# esp8266_ver3.net
KiCad netlist of a schematic drawn in EAGLE
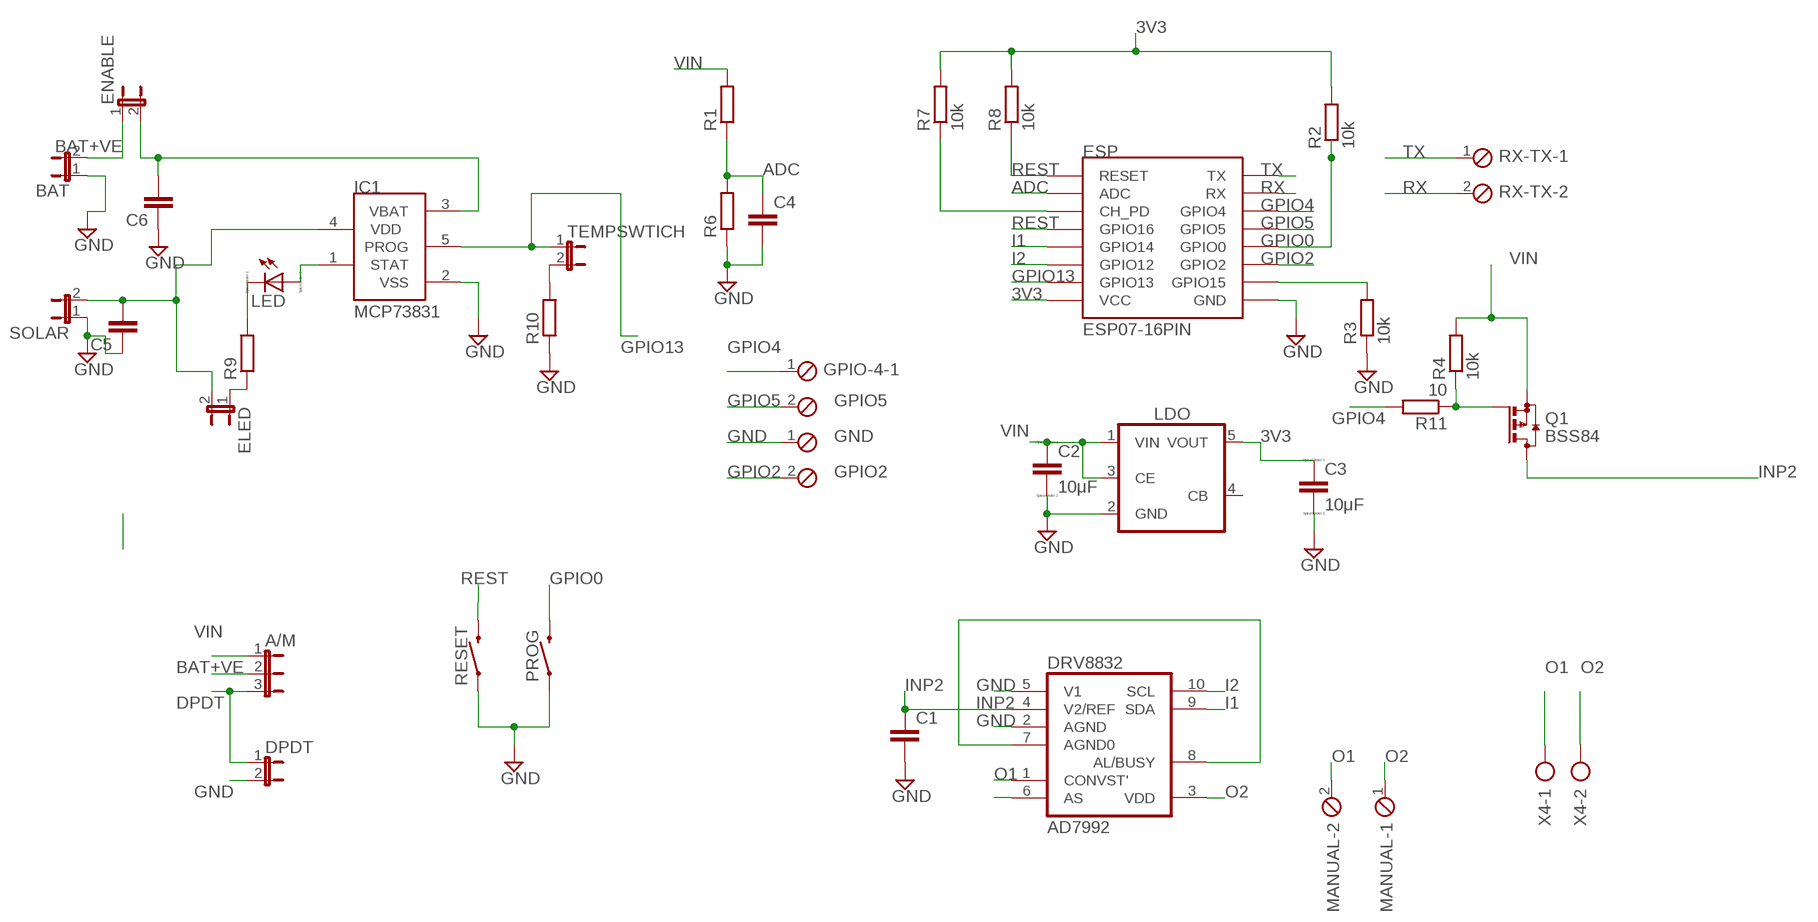
[diagram p0: schematic, sheet 1]

(export (version "E")
  (design (tool "Eeschema 10.0.6"))
  (components
    (comp (ref "A/M")
      (value "JP2E")
      (footprint "eagle-import:JP2")
      (libsource (lib "eagle-import") (part "JP2E"))
    )
    (comp (ref "BAT")
      (value "JP1E")
      (footprint "eagle-import:JP1")
      (libsource (lib "eagle-import") (part "JP1E"))
    )
    (comp (ref "C1")
      (value "C-EUC0805K")
      (footprint "eagle-import:C0805K")
      (libsource (lib "eagle-import") (part "C-EUC0805K"))
    )
    (comp (ref "C2")
      (value "10μF")
      (footprint "eagle-import:C1206")
      (libsource (lib "eagle-import") (part "CC1206"))
    )
    (comp (ref "C3")
      (value "10μF")
      (footprint "eagle-import:C1206")
      (libsource (lib "eagle-import") (part "CC1206"))
    )
    (comp (ref "C4")
      (value "C-EUC1206")
      (footprint "eagle-import:C1206")
      (libsource (lib "eagle-import") (part "C-EUC1206"))
    )
    (comp (ref "C5")
      (value "C-EUC1206")
      (footprint "eagle-import:C1206")
      (libsource (lib "eagle-import") (part "C-EUC1206"))
    )
    (comp (ref "C6")
      (value "C-EUC1206")
      (footprint "eagle-import:C1206")
      (libsource (lib "eagle-import") (part "C-EUC1206"))
    )
    (comp (ref "DPDT")
      (value "JP1E")
      (footprint "eagle-import:JP1")
      (libsource (lib "eagle-import") (part "JP1E"))
    )
    (comp (ref "DRV8832")
      (value "AD7992")
      (footprint "eagle-import:MSOP10")
      (libsource (lib "eagle-import") (part "AD7992"))
    )
    (comp (ref "ELED")
      (value "JP1E")
      (footprint "eagle-import:JP1")
      (libsource (lib "eagle-import") (part "JP1E"))
    )
    (comp (ref "ENABLE")
      (value "JP1E")
      (footprint "eagle-import:JP1")
      (libsource (lib "eagle-import") (part "JP1E"))
    )
    (comp (ref "ESP")
      (value "ESP07-16PIN")
      (footprint "eagle-import:ESP07-16PIN")
      (libsource (lib "eagle-import") (part "ESP07-16PIN"))
    )
    (comp (ref "GPIO-4")
      (value "MPT2")
      (footprint "eagle-import:2POL254")
      (libsource (lib "eagle-import") (part "con-phoenix-254_172_MPT2"))
    )
    (comp (ref "IC1")
      (value "MCP73831")
      (footprint "eagle-import:SOT23-5L")
      (libsource (lib "eagle-import") (part "MCP73831"))
    )
    (comp (ref "LDO")
      (value "TS5205")
      (footprint "eagle-import:SOT25")
      (libsource (lib "eagle-import") (part "TS5205"))
    )
    (comp (ref "LED")
      (value "LED_E")
      (footprint "eagle-import:LED_1206")
      (libsource (lib "eagle-import") (part "LED_E"))
    )
    (comp (ref "MANUAL")
      (value "MPT2")
      (footprint "eagle-import:2POL254")
      (libsource (lib "eagle-import") (part "con-phoenix-254_172_MPT2"))
    )
    (comp (ref "PROG")
      (value "MOMENTARY-SWITCH-SPST-SMD-5.2MM")
      (footprint "eagle-import:TACTILE_SWITCH_SMD_5.2MM")
      (libsource (lib "eagle-import") (part "MOMENTARY-SWITCH-SPST-SMD-5.2MM"))
    )
    (comp (ref "Q1")
      (value "BSS84")
      (footprint "eagle-import:SOT23")
      (libsource (lib "eagle-import") (part "BSS84"))
    )
    (comp (ref "R1")
      (value "R-EU_R1206")
      (footprint "eagle-import:R1206")
      (libsource (lib "eagle-import") (part "resistor_348_R-EU_R1206"))
    )
    (comp (ref "R2")
      (value "10k")
      (footprint "eagle-import:R1206")
      (libsource (lib "eagle-import") (part "R-EU_R1206"))
    )
    (comp (ref "R3")
      (value "10k")
      (footprint "eagle-import:R1206")
      (libsource (lib "eagle-import") (part "R-EU_R1206"))
    )
    (comp (ref "R4")
      (value "10k")
      (footprint "eagle-import:R1206")
      (libsource (lib "eagle-import") (part "resistor_348_R-EU_R1206"))
    )
    (comp (ref "R6")
      (value "R-EU_R1206")
      (footprint "eagle-import:R1206")
      (libsource (lib "eagle-import") (part "resistor_348_R-EU_R1206"))
    )
    (comp (ref "R7")
      (value "10k")
      (footprint "eagle-import:R1206")
      (libsource (lib "eagle-import") (part "R-EU_R1206"))
    )
    (comp (ref "R8")
      (value "10k")
      (footprint "eagle-import:R1206")
      (libsource (lib "eagle-import") (part "R-EU_R1206"))
    )
    (comp (ref "R9")
      (value "R-EU_R1206")
      (footprint "eagle-import:R1206")
      (libsource (lib "eagle-import") (part "resistor_348_R-EU_R1206"))
    )
    (comp (ref "R10")
      (value "R-EU_R1206")
      (footprint "eagle-import:R1206")
      (libsource (lib "eagle-import") (part "resistor_348_R-EU_R1206"))
    )
    (comp (ref "R11")
      (value "10")
      (footprint "eagle-import:R1206")
      (libsource (lib "eagle-import") (part "resistor_348_R-EU_R1206"))
    )
    (comp (ref "RESET")
      (value "MOMENTARY-SWITCH-SPST-SMD-5.2MM")
      (footprint "eagle-import:TACTILE_SWITCH_SMD_5.2MM")
      (libsource (lib "eagle-import") (part "MOMENTARY-SWITCH-SPST-SMD-5.2MM"))
    )
    (comp (ref "RX-TX")
      (value "MPT2")
      (footprint "eagle-import:2POL254")
      (libsource (lib "eagle-import") (part "MPT2"))
    )
    (comp (ref "SOLAR")
      (value "JP1E")
      (footprint "eagle-import:JP1")
      (libsource (lib "eagle-import") (part "JP1E"))
    )
    (comp (ref "TEMPSWTICH")
      (value "JP1E")
      (footprint "eagle-import:JP1")
      (libsource (lib "eagle-import") (part "JP1E"))
    )
    (comp (ref "X2")
      (value "MPT2")
      (footprint "eagle-import:2POL254")
      (libsource (lib "eagle-import") (part "con-phoenix-254_172_MPT2"))
    )
    (comp (ref "X4")
      (value "AK300/2")
      (footprint "eagle-import:AK300_2")
      (libsource (lib "eagle-import") (part "AK300/2"))
    )
  )
  (nets
    (net (code "1") (name "/3V3") (class "Default")
      (node (ref "C3") (pin "1") (pinfunction "1_1") (pintype "passive"))
      (node (ref "ESP") (pin "VCC") (pinfunction "VCC_VCC") (pintype "bidirectional"))
      (node (ref "LDO") (pin "5") (pinfunction "VOUT_5") (pintype "passive"))
      (node (ref "R2") (pin "2") (pinfunction "2_2") (pintype "passive"))
      (node (ref "R7") (pin "2") (pinfunction "2_2") (pintype "passive"))
      (node (ref "R8") (pin "2") (pinfunction "2_2") (pintype "passive"))
    )
    (net (code "2") (name "/ADC") (class "Default")
      (node (ref "C4") (pin "1") (pinfunction "1_1") (pintype "passive"))
      (node (ref "ESP") (pin "ADC") (pinfunction "ADC_ADC") (pintype "bidirectional"))
      (node (ref "R1") (pin "1") (pinfunction "1_1") (pintype "passive"))
      (node (ref "R6") (pin "2") (pinfunction "2_2") (pintype "passive"))
    )
    (net (code "3") (name "/BAT+VE") (class "Default")
      (node (ref "A/M") (pin "2") (pinfunction "2_2") (pintype "passive"))
      (node (ref "BAT") (pin "2") (pinfunction "2_2") (pintype "passive"))
      (node (ref "ENABLE") (pin "1") (pinfunction "1_1") (pintype "passive"))
    )
    (net (code "4") (name "/DPDT") (class "Default")
      (node (ref "A/M") (pin "3") (pinfunction "3_3") (pintype "passive"))
      (node (ref "DPDT") (pin "1") (pinfunction "1_1") (pintype "passive"))
    )
    (net (code "5") (name "/GPIO0") (class "Default")
      (node (ref "ESP") (pin "GPIO0") (pinfunction "GPIO0_GPIO0") (pintype "bidirectional"))
      (node (ref "PROG") (pin "3") (pinfunction "2_3") (pintype "passive"))
      (node (ref "R2") (pin "1") (pinfunction "1_1") (pintype "passive"))
    )
    (net (code "6") (name "/GPIO2") (class "Default")
      (node (ref "ESP") (pin "GPIO2") (pinfunction "GPIO2_GPIO2") (pintype "bidirectional"))
      (node (ref "X2") (pin "2") (pinfunction "1_2") (pintype "passive"))
    )
    (net (code "7") (name "/GPIO4") (class "Default")
      (node (ref "ESP") (pin "GPIO4") (pinfunction "GPIO4_GPIO4") (pintype "bidirectional"))
      (node (ref "GPIO-4") (pin "1") (pinfunction "1_1") (pintype "passive"))
      (node (ref "R11") (pin "2") (pinfunction "2_2") (pintype "passive"))
    )
    (net (code "8") (name "/GPIO5") (class "Default")
      (node (ref "ESP") (pin "GPIO5") (pinfunction "GPIO5_GPIO5") (pintype "bidirectional"))
      (node (ref "GPIO-4") (pin "2") (pinfunction "1_2") (pintype "passive"))
    )
    (net (code "9") (name "/GPIO13") (class "Default")
      (node (ref "ESP") (pin "GPIO13") (pinfunction "GPIO13_GPIO13") (pintype "bidirectional"))
      (node (ref "IC1") (pin "5") (pinfunction "PROG_5") (pintype "bidirectional"))
      (node (ref "TEMPSWTICH") (pin "1") (pinfunction "1_1") (pintype "passive"))
    )
    (net (code "10") (name "/I1") (class "Default")
      (node (ref "DRV8832") (pin "9") (pinfunction "SDA_9") (pintype "output"))
      (node (ref "ESP") (pin "GPIO14") (pinfunction "GPIO14_GPIO14") (pintype "bidirectional"))
    )
    (net (code "11") (name "/I2") (class "Default")
      (node (ref "DRV8832") (pin "10") (pinfunction "SCL_10") (pintype "output"))
      (node (ref "ESP") (pin "GPIO12") (pinfunction "GPIO12_GPIO12") (pintype "bidirectional"))
    )
    (net (code "12") (name "/INP2") (class "Default")
      (node (ref "C1") (pin "1") (pinfunction "1_1") (pintype "passive"))
      (node (ref "DRV8832") (pin "4") (pinfunction "V2/REF_4") (pintype "input"))
      (node (ref "Q1") (pin "3") (pinfunction "D_3") (pintype "passive"))
    )
    (net (code "13") (name "/O1") (class "Default")
      (node (ref "DRV8832") (pin "1") (pinfunction "CONVST'_1") (pintype "input"))
      (node (ref "MANUAL") (pin "2") (pinfunction "1_2") (pintype "passive"))
      (node (ref "X4") (pin "1") (pinfunction "KL_1") (pintype "passive"))
    )
    (net (code "14") (name "/O2") (class "Default")
      (node (ref "DRV8832") (pin "3") (pinfunction "VDD_3") (pintype "power_in"))
      (node (ref "MANUAL") (pin "1") (pinfunction "1_1") (pintype "passive"))
      (node (ref "X4") (pin "2") (pinfunction "KL_2") (pintype "passive"))
    )
    (net (code "15") (name "/REST") (class "Default")
      (node (ref "ESP") (pin "GPIO16") (pinfunction "GPIO16_GPIO16") (pintype "bidirectional"))
      (node (ref "ESP") (pin "REST") (pinfunction "RESET_REST") (pintype "bidirectional"))
      (node (ref "R8") (pin "1") (pinfunction "1_1") (pintype "passive"))
      (node (ref "RESET") (pin "3") (pinfunction "2_3") (pintype "passive"))
    )
    (net (code "16") (name "/RX") (class "Default")
      (node (ref "ESP") (pin "RX") (pinfunction "RX_RX") (pintype "bidirectional"))
      (node (ref "RX-TX") (pin "2") (pinfunction "1_2") (pintype "passive"))
    )
    (net (code "17") (name "/TX") (class "Default")
      (node (ref "ESP") (pin "TX") (pinfunction "TX_TX") (pintype "bidirectional"))
      (node (ref "RX-TX") (pin "1") (pinfunction "1_1") (pintype "passive"))
    )
    (net (code "18") (name "/VIN") (class "Default")
      (node (ref "A/M") (pin "1") (pinfunction "1_1") (pintype "passive"))
      (node (ref "C2") (pin "1") (pinfunction "1_1") (pintype "passive"))
      (node (ref "LDO") (pin "1") (pinfunction "VIN_1") (pintype "input"))
      (node (ref "LDO") (pin "3") (pinfunction "CE_3") (pintype "input"))
      (node (ref "Q1") (pin "2") (pinfunction "S_2") (pintype "passive"))
      (node (ref "R1") (pin "2") (pinfunction "2_2") (pintype "passive"))
      (node (ref "R4") (pin "2") (pinfunction "2_2") (pintype "passive"))
    )
    (net (code "19") (name "GND") (class "Default")
      (node (ref "BAT") (pin "1") (pinfunction "1_1") (pintype "passive"))
      (node (ref "C1") (pin "2") (pinfunction "2_2") (pintype "passive"))
      (node (ref "C2") (pin "2") (pinfunction "2_2") (pintype "passive"))
      (node (ref "C3") (pin "2") (pinfunction "2_2") (pintype "passive"))
      (node (ref "C4") (pin "2") (pinfunction "2_2") (pintype "passive"))
      (node (ref "C5") (pin "1") (pinfunction "1_1") (pintype "passive"))
      (node (ref "C6") (pin "1") (pinfunction "1_1") (pintype "passive"))
      (node (ref "DPDT") (pin "2") (pinfunction "2_2") (pintype "passive"))
      (node (ref "DRV8832") (pin "2") (pinfunction "AGND_2") (pintype "power_in"))
      (node (ref "DRV8832") (pin "5") (pinfunction "V1_5") (pintype "input"))
      (node (ref "ESP") (pin "GND") (pinfunction "GND_GND") (pintype "bidirectional"))
      (node (ref "IC1") (pin "2") (pinfunction "VSS_2") (pintype "bidirectional"))
      (node (ref "LDO") (pin "2") (pinfunction "GND_2") (pintype "passive"))
      (node (ref "PROG") (pin "1") (pinfunction "1_1") (pintype "passive"))
      (node (ref "R10") (pin "1") (pinfunction "1_1") (pintype "passive"))
      (node (ref "R3") (pin "1") (pinfunction "1_1") (pintype "passive"))
      (node (ref "R6") (pin "1") (pinfunction "1_1") (pintype "passive"))
      (node (ref "RESET") (pin "1") (pinfunction "1_1") (pintype "passive"))
      (node (ref "SOLAR") (pin "1") (pinfunction "1_1") (pintype "passive"))
      (node (ref "X2") (pin "1") (pinfunction "1_1") (pintype "passive"))
    )
    (net (code "20") (name "Net-(DRV8832-AGND0)") (class "Default")
      (node (ref "DRV8832") (pin "7") (pinfunction "AGND0_7") (pintype "power_in"))
      (node (ref "DRV8832") (pin "8") (pinfunction "AL/BUSY_8") (pintype "output"))
    )
    (net (code "21") (name "Net-(ELED-Pad1)") (class "Default")
      (node (ref "ELED") (pin "1") (pinfunction "1_1") (pintype "passive"))
      (node (ref "R9") (pin "1") (pinfunction "1_1") (pintype "passive"))
    )
    (net (code "22") (name "Net-(ESP-PadCH_PD)") (class "Default")
      (node (ref "ESP") (pin "CH_PD") (pinfunction "CH_PD_CH_PD") (pintype "bidirectional"))
      (node (ref "R7") (pin "1") (pinfunction "1_1") (pintype "passive"))
    )
    (net (code "23") (name "Net-(ESP-PadGPIO15)") (class "Default")
      (node (ref "ESP") (pin "GPIO15") (pinfunction "GPIO15_GPIO15") (pintype "bidirectional"))
      (node (ref "R3") (pin "2") (pinfunction "2_2") (pintype "passive"))
    )
    (net (code "24") (name "Net-(IC1-STAT)") (class "Default")
      (node (ref "IC1") (pin "1") (pinfunction "STAT_1") (pintype "bidirectional"))
      (node (ref "LED") (pin "A") (pinfunction "A_A") (pintype "passive"))
    )
    (net (code "25") (name "Net-(IC1-VBAT)") (class "Default")
      (node (ref "C6") (pin "2") (pinfunction "2_2") (pintype "passive"))
      (node (ref "ENABLE") (pin "2") (pinfunction "2_2") (pintype "passive"))
      (node (ref "IC1") (pin "3") (pinfunction "VBAT_3") (pintype "bidirectional"))
    )
    (net (code "26") (name "Net-(IC1-VDD)") (class "Default")
      (node (ref "C5") (pin "2") (pinfunction "2_2") (pintype "passive"))
      (node (ref "ELED") (pin "2") (pinfunction "2_2") (pintype "passive"))
      (node (ref "IC1") (pin "4") (pinfunction "VDD_4") (pintype "bidirectional"))
      (node (ref "SOLAR") (pin "2") (pinfunction "2_2") (pintype "passive"))
    )
    (net (code "27") (name "Net-(LED-PadC)") (class "Default")
      (node (ref "LED") (pin "C") (pinfunction "C_C") (pintype "passive"))
      (node (ref "R9") (pin "2") (pinfunction "2_2") (pintype "passive"))
    )
    (net (code "28") (name "Net-(Q1-G)") (class "Default")
      (node (ref "Q1") (pin "1") (pinfunction "G_1") (pintype "passive"))
      (node (ref "R11") (pin "1") (pinfunction "1_1") (pintype "passive"))
      (node (ref "R4") (pin "1") (pinfunction "1_1") (pintype "passive"))
    )
    (net (code "29") (name "Net-(R10-Pad2)") (class "Default")
      (node (ref "R10") (pin "2") (pinfunction "2_2") (pintype "passive"))
      (node (ref "TEMPSWTICH") (pin "2") (pinfunction "2_2") (pintype "passive"))
    )
    (net (code "30") (name "unconnected-(DRV8832-AS-Pad6)") (class "Default")
      (node (ref "DRV8832") (pin "6") (pinfunction "AS_6") (pintype "input"))
    )
    (net (code "31") (name "unconnected-(LDO-CB-Pad4)") (class "Default")
      (node (ref "LDO") (pin "4") (pinfunction "CB_4") (pintype "input"))
    )
  )
)
